# schematic.net
KiCad netlist of a schematic drawn in Altium Designer
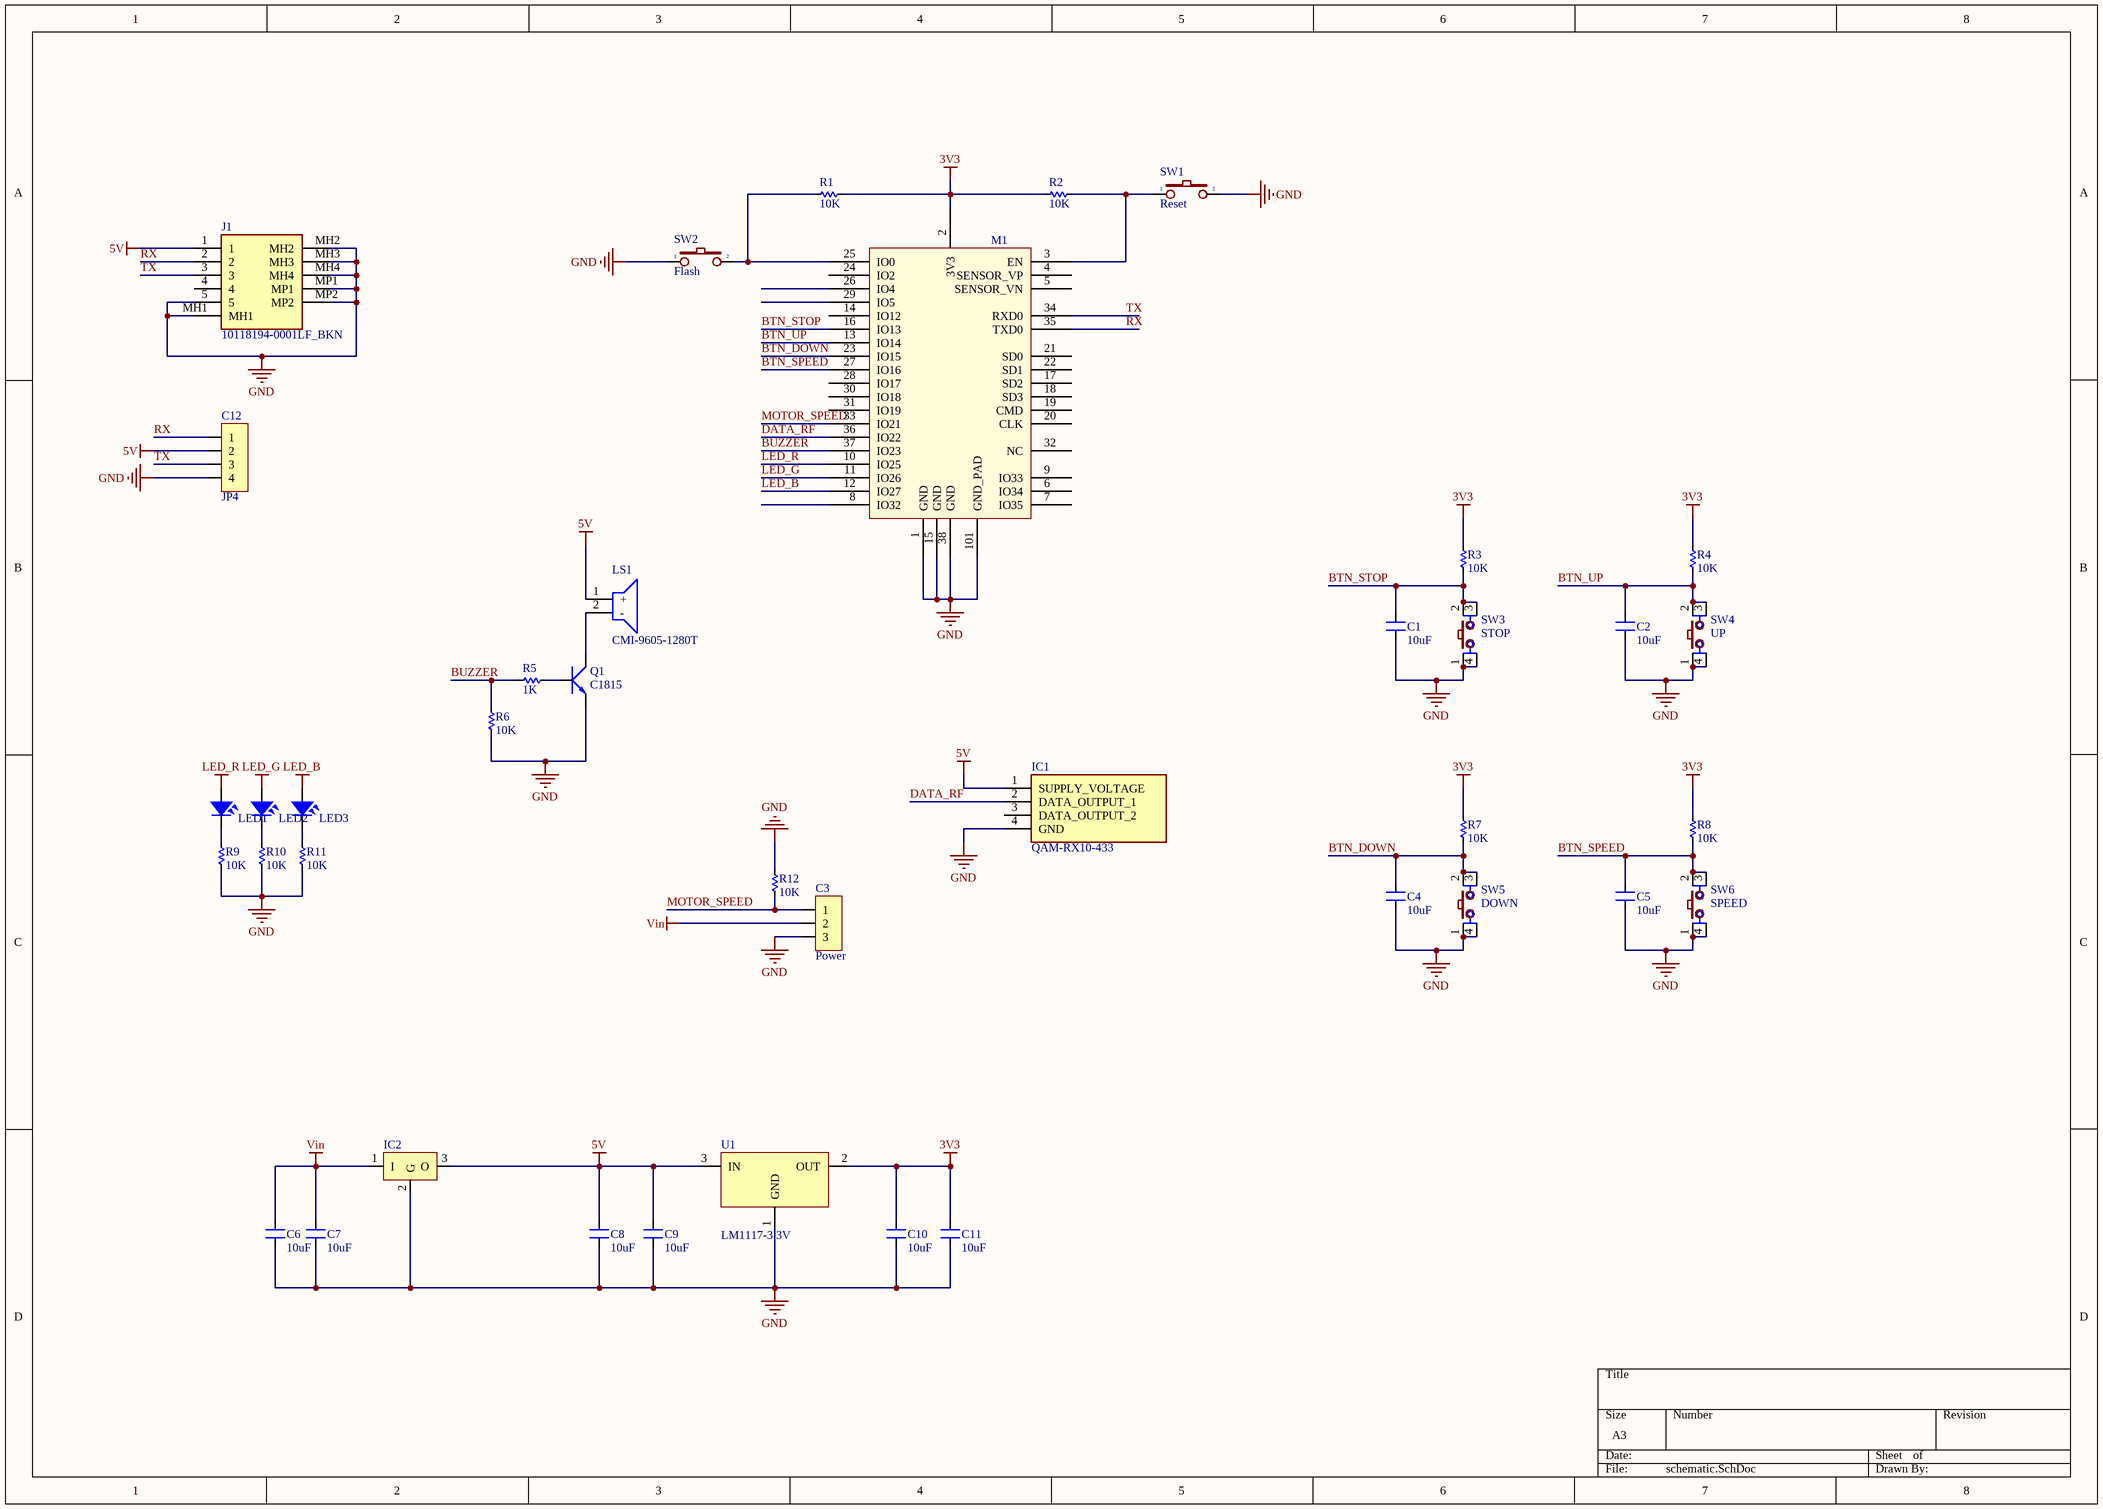
[diagram p0: schematic.SchDoc]

(export (version "E")
  (design (tool "Eeschema 10.0.6"))
  (components
    (comp (ref "C1")
      (value "10uF")
      (footprint "CN-SMD-0603")
      (description "Tu gom")
      (libsource (lib "LIBTanCN") (part "CN"))
    )
    (comp (ref "C2")
      (value "10uF")
      (footprint "CN-SMD-0603")
      (description "Tu gom")
      (libsource (lib "LIBTanCN") (part "CN"))
    )
    (comp (ref "C3")
      (value "Power")
      (footprint "JP3-D1C")
      (description "WR-PHD 2.54 mm Angled Socket Header")
      (fields
        (field (name "MANUFACTURER") "Würth Elektronik eiSos GmbH")
        (field (name "PARTNO") "613003143121")
        (field (name "CREATED BY") "Karrer Zheng")
      )
      (libsource (lib "LIBRARY") (part "JP3"))
    )
    (comp (ref "C4")
      (value "10uF")
      (footprint "CN-SMD-0603")
      (description "Tu gom")
      (libsource (lib "LIBTanCN") (part "CN"))
    )
    (comp (ref "C5")
      (value "10uF")
      (footprint "CN-SMD-0603")
      (description "Tu gom")
      (libsource (lib "LIBTanCN") (part "CN"))
    )
    (comp (ref "C6")
      (value "10uF")
      (footprint "CN-SMD-0603")
      (description "Tu gom")
      (libsource (lib "LIBTanCN") (part "CN"))
    )
    (comp (ref "C7")
      (value "10uF")
      (footprint "CN-SMD-0603")
      (description "Tu gom")
      (libsource (lib "LIBTanCN") (part "CN"))
    )
    (comp (ref "C8")
      (value "10uF")
      (footprint "CN-SMD-0603")
      (description "Tu gom")
      (libsource (lib "LIBTanCN") (part "CN"))
    )
    (comp (ref "C9")
      (value "10uF")
      (footprint "CN-SMD-0603")
      (description "Tu gom")
      (libsource (lib "LIBTanCN") (part "CN"))
    )
    (comp (ref "C10")
      (value "10uF")
      (footprint "CN-SMD-0603")
      (description "Tu gom")
      (libsource (lib "LIBTanCN") (part "CN"))
    )
    (comp (ref "C11")
      (value "10uF")
      (footprint "CN-SMD-0603")
      (description "Tu gom")
      (libsource (lib "LIBTanCN") (part "CN"))
    )
    (comp (ref "C12")
      (value "JP4")
      (footprint "JP4-C1T")
      (description "WR-PHD 2.54 mm Angled Socket Header")
      (fields
        (field (name "MANUFACTURER") "Würth Elektronik eiSos GmbH")
        (field (name "PARTNO") "613004143121")
        (field (name "CREATED BY") "Karrer Zheng")
      )
      (libsource (lib "LIBRARY") (part "JP4"))
    )
    (comp (ref "IC1")
      (value "QAM-RX10-433")
      (footprint "SamacSys:QAMRX10433")
      (description "Integrated Circuit")
      (fields (field (name "MOUSER PART NUMBER") "223-QAM-RX10-433"))
      (libsource (lib "*") (part "QAM-RX10-433"))
    )
    (comp (ref "IC2")
      (value "LM78xx")
      (footprint "TO252-123")
      (description "Positive Voltage Regulator")
      (fields (field (name "PUBLISHER") "Altium Limited"))
      (libsource (lib "LIBRARY") (part "LM78xx"))
    )
    (comp (ref "J1")
      (value "10118194-0001LF_BKN")
      (footprint "SamacSys:101181940001LFBKN")
      (description "Connector")
      (fields (field (name "MANUFACTURER_PART_NUMBER") "10118194-0001LF/BKN"))
      (libsource (lib "*") (part "10118194-0001LF_BKN"))
    )
    (comp (ref "LED1")
      (value "LED")
      (footprint "LED-3MM-BLUE")
      (description "LED Single colour Green and Red")
      (libsource (lib "LIBRARY") (part "LED"))
    )
    (comp (ref "LED2")
      (value "LED")
      (footprint "LED-3MM-BLUE")
      (description "LED Single colour Green and Red")
      (libsource (lib "LIBRARY") (part "LED"))
    )
    (comp (ref "LED3")
      (value "LED")
      (footprint "LED-3MM-BLUE")
      (description "LED Single colour Green and Red")
      (libsource (lib "LIBRARY") (part "LED"))
    )
    (comp (ref "LS1")
      (value "CMI-9605-1280T")
      (footprint "SamacSys:CMI96051280T")
      (description "Loudspeaker or Buzzer")
      (fields (field (name "MOUSER PART NUMBER") "490-CMI-9605-1280T"))
      (libsource (lib "SamacSys") (part "CMI-9605-1280T"))
    )
    (comp (ref "M1")
      (value "ESP32S_Module")
      (footprint "ESP32S")
      (description "Esp-32S")
      (libsource (lib "ESP32S") (part "ESP32S_Module"))
    )
    (comp (ref "Q1")
      (value "C1815")
      (footprint "SOT23B")
      (description "NPN 600mW, ECB")
      (libsource (lib "electronicvn-library1") (part "C1815"))
    )
    (comp (ref "R1")
      (value "10K")
      (footprint "RES-SMD-0603")
      (description "Resistor")
      (fields
        (field (name "MANUFACTURER") "Generic Components")
        (field (name "PUBLISHER") "Altium Hobart Technology Centre")
      )
      (libsource (lib "LIBRARY") (part "Res-SMD"))
    )
    (comp (ref "R2")
      (value "10K")
      (footprint "RES-SMD-0603")
      (description "Resistor")
      (fields
        (field (name "MANUFACTURER") "Generic Components")
        (field (name "PUBLISHER") "Altium Hobart Technology Centre")
      )
      (libsource (lib "LIBRARY") (part "Res-SMD"))
    )
    (comp (ref "R3")
      (value "10K")
      (footprint "RES-SMD-0603")
      (description "Resistor")
      (fields
        (field (name "MANUFACTURER") "Generic Components")
        (field (name "PUBLISHER") "Altium Hobart Technology Centre")
      )
      (libsource (lib "LIBRARY") (part "Res-SMD"))
    )
    (comp (ref "R4")
      (value "10K")
      (footprint "RES-SMD-0603")
      (description "Resistor")
      (fields
        (field (name "MANUFACTURER") "Generic Components")
        (field (name "PUBLISHER") "Altium Hobart Technology Centre")
      )
      (libsource (lib "LIBRARY") (part "Res-SMD"))
    )
    (comp (ref "R5")
      (value "1K")
      (footprint "RES-SMD-0603")
      (description "Resistor")
      (fields
        (field (name "MANUFACTURER") "Generic Components")
        (field (name "PUBLISHER") "Altium Hobart Technology Centre")
      )
      (libsource (lib "LIBRARY") (part "Res-SMD"))
    )
    (comp (ref "R6")
      (value "10K")
      (footprint "RES-SMD-0603")
      (description "Resistor")
      (fields
        (field (name "MANUFACTURER") "Generic Components")
        (field (name "PUBLISHER") "Altium Hobart Technology Centre")
      )
      (libsource (lib "LIBRARY") (part "Res-SMD"))
    )
    (comp (ref "R7")
      (value "10K")
      (footprint "RES-SMD-0603")
      (description "Resistor")
      (fields
        (field (name "MANUFACTURER") "Generic Components")
        (field (name "PUBLISHER") "Altium Hobart Technology Centre")
      )
      (libsource (lib "LIBRARY") (part "Res-SMD"))
    )
    (comp (ref "R8")
      (value "10K")
      (footprint "RES-SMD-0603")
      (description "Resistor")
      (fields
        (field (name "MANUFACTURER") "Generic Components")
        (field (name "PUBLISHER") "Altium Hobart Technology Centre")
      )
      (libsource (lib "LIBRARY") (part "Res-SMD"))
    )
    (comp (ref "R9")
      (value "10K")
      (footprint "RES-SMD-0603")
      (description "Resistor")
      (fields
        (field (name "MANUFACTURER") "Generic Components")
        (field (name "PUBLISHER") "Altium Hobart Technology Centre")
      )
      (libsource (lib "LIBRARY") (part "Res-SMD"))
    )
    (comp (ref "R10")
      (value "10K")
      (footprint "RES-SMD-0603")
      (description "Resistor")
      (fields
        (field (name "MANUFACTURER") "Generic Components")
        (field (name "PUBLISHER") "Altium Hobart Technology Centre")
      )
      (libsource (lib "LIBRARY") (part "Res-SMD"))
    )
    (comp (ref "R11")
      (value "10K")
      (footprint "RES-SMD-0603")
      (description "Resistor")
      (fields
        (field (name "MANUFACTURER") "Generic Components")
        (field (name "PUBLISHER") "Altium Hobart Technology Centre")
      )
      (libsource (lib "LIBRARY") (part "Res-SMD"))
    )
    (comp (ref "R12")
      (value "10K")
      (footprint "RES-SMD-0603")
      (description "Resistor")
      (fields
        (field (name "MANUFACTURER") "Generic Components")
        (field (name "PUBLISHER") "Altium Hobart Technology Centre")
      )
      (libsource (lib "LIBRARY") (part "Res-SMD"))
    )
    (comp (ref "SW1")
      (value "Reset")
      (footprint "SW1-SMD")
      (description "Switch button 2 pin")
      (libsource (lib "LIBRARY") (part "SW2"))
    )
    (comp (ref "SW2")
      (value "Flash")
      (footprint "SW-DIP1-1")
      (description "Switch button 2 pin")
      (libsource (lib "LIBRARY") (part "SW2"))
    )
    (comp (ref "SW3")
      (value "STOP")
      (footprint "SW2-SMD")
      (description "Switch button 4 pin")
      (libsource (lib "LIBRARY") (part "SW4"))
    )
    (comp (ref "SW4")
      (value "UP")
      (footprint "SW2-SMD")
      (description "Switch button 4 pin")
      (libsource (lib "LIBRARY") (part "SW4"))
    )
    (comp (ref "SW5")
      (value "DOWN")
      (footprint "SW2-SMD")
      (description "Switch button 4 pin")
      (libsource (lib "LIBRARY") (part "SW4"))
    )
    (comp (ref "SW6")
      (value "SPEED")
      (footprint "SW2-SMD")
      (description "Switch button 4 pin")
      (libsource (lib "LIBRARY") (part "SW4"))
    )
    (comp (ref "U1")
      (value "LM1117-3.3V")
      (footprint "SOT223")
      (description "800mA Low-Dropout Linear Regulator")
      (fields (field (name "CREATOR") "Nguyen Ba Bien"))
      (libsource (lib "LIBRARY") (part "LM1117"))
    )
  )
  (nets
    (net (code "1") (name "/BTN_DOWN") (class "Default")
      (node (ref "C4") (pin "1") (pinfunction "1_1") (pintype "passive"))
      (node (ref "M1") (pin "23") (pinfunction "IO15_23") (pintype "passive"))
      (node (ref "R7") (pin "2") (pinfunction "2_2") (pintype "passive"))
      (node (ref "SW5") (pin "2") (pinfunction "2_2") (pintype "passive"))
      (node (ref "SW5") (pin "3") (pinfunction "3_3") (pintype "passive"))
    )
    (net (code "2") (name "/BTN_SPEED") (class "Default")
      (node (ref "C5") (pin "1") (pinfunction "1_1") (pintype "passive"))
      (node (ref "M1") (pin "27") (pinfunction "IO16_27") (pintype "passive"))
      (node (ref "R8") (pin "2") (pinfunction "2_2") (pintype "passive"))
      (node (ref "SW6") (pin "2") (pinfunction "2_2") (pintype "passive"))
      (node (ref "SW6") (pin "3") (pinfunction "3_3") (pintype "passive"))
    )
    (net (code "3") (name "/BTN_STOP") (class "Default")
      (node (ref "C1") (pin "1") (pinfunction "1_1") (pintype "passive"))
      (node (ref "M1") (pin "16") (pinfunction "IO13_16") (pintype "passive"))
      (node (ref "R3") (pin "2") (pinfunction "2_2") (pintype "passive"))
      (node (ref "SW3") (pin "2") (pinfunction "2_2") (pintype "passive"))
      (node (ref "SW3") (pin "3") (pinfunction "3_3") (pintype "passive"))
    )
    (net (code "4") (name "/BTN_UP") (class "Default")
      (node (ref "C2") (pin "1") (pinfunction "1_1") (pintype "passive"))
      (node (ref "M1") (pin "13") (pinfunction "IO14_13") (pintype "passive"))
      (node (ref "R4") (pin "2") (pinfunction "2_2") (pintype "passive"))
      (node (ref "SW4") (pin "2") (pinfunction "2_2") (pintype "passive"))
      (node (ref "SW4") (pin "3") (pinfunction "3_3") (pintype "passive"))
    )
    (net (code "5") (name "/BUZZER") (class "Default")
      (node (ref "M1") (pin "37") (pinfunction "IO23_37") (pintype "passive"))
      (node (ref "R5") (pin "2") (pinfunction "2_2") (pintype "passive"))
      (node (ref "R6") (pin "1") (pinfunction "1_1") (pintype "passive"))
    )
    (net (code "6") (name "/DATA_RF") (class "Default")
      (node (ref "IC1") (pin "2") (pinfunction "DATA_OUTPUT_1_2") (pintype "passive"))
      (node (ref "M1") (pin "36") (pinfunction "IO22_36") (pintype "passive"))
    )
    (net (code "7") (name "/MOTOR_SPEED") (class "Default")
      (node (ref "C3") (pin "1") (pinfunction "1_1") (pintype "passive"))
      (node (ref "M1") (pin "33") (pinfunction "IO21_33") (pintype "passive"))
      (node (ref "R12") (pin "2") (pinfunction "2_2") (pintype "passive"))
    )
    (net (code "8") (name "/RX") (class "Default")
      (node (ref "C12") (pin "1") (pinfunction "1_1") (pintype "passive"))
      (node (ref "J1") (pin "2") (pinfunction "2_2") (pintype "passive"))
      (node (ref "M1") (pin "35") (pinfunction "TXD0_35") (pintype "passive"))
    )
    (net (code "9") (name "/TX") (class "Default")
      (node (ref "C12") (pin "3") (pinfunction "3_3") (pintype "passive"))
      (node (ref "J1") (pin "3") (pinfunction "3_3") (pintype "passive"))
      (node (ref "M1") (pin "34") (pinfunction "RXD0_34") (pintype "passive"))
    )
    (net (code "10") (name "3V3") (class "Default")
      (node (ref "C10") (pin "1") (pinfunction "1_1") (pintype "passive"))
      (node (ref "C11") (pin "1") (pinfunction "1_1") (pintype "passive"))
      (node (ref "M1") (pin "2") (pinfunction "3V3_2") (pintype "power_in"))
      (node (ref "R1") (pin "1") (pinfunction "1_1") (pintype "passive"))
      (node (ref "R2") (pin "2") (pinfunction "2_2") (pintype "passive"))
      (node (ref "R3") (pin "1") (pinfunction "1_1") (pintype "passive"))
      (node (ref "R4") (pin "1") (pinfunction "1_1") (pintype "passive"))
      (node (ref "R7") (pin "1") (pinfunction "1_1") (pintype "passive"))
      (node (ref "R8") (pin "1") (pinfunction "1_1") (pintype "passive"))
      (node (ref "U1") (pin "2") (pinfunction "OUT_2") (pintype "passive"))
    )
    (net (code "11") (name "5V") (class "Default")
      (node (ref "C12") (pin "2") (pinfunction "2_2") (pintype "passive"))
      (node (ref "C8") (pin "1") (pinfunction "1_1") (pintype "passive"))
      (node (ref "C9") (pin "1") (pinfunction "1_1") (pintype "passive"))
      (node (ref "IC1") (pin "1") (pinfunction "SUPPLY_VOLTAGE_1") (pintype "passive"))
      (node (ref "IC2") (pin "3") (pinfunction "O_3") (pintype "power_in"))
      (node (ref "J1") (pin "1") (pinfunction "1_1") (pintype "passive"))
      (node (ref "LS1") (pin "1") (pinfunction "+_1") (pintype "passive"))
      (node (ref "U1") (pin "3") (pinfunction "IN_3") (pintype "passive"))
    )
    (net (code "12") (name "GND") (class "Default")
      (node (ref "C1") (pin "2") (pinfunction "2_2") (pintype "passive"))
      (node (ref "C10") (pin "2") (pinfunction "2_2") (pintype "passive"))
      (node (ref "C11") (pin "2") (pinfunction "2_2") (pintype "passive"))
      (node (ref "C12") (pin "4") (pinfunction "4_4") (pintype "passive"))
      (node (ref "C2") (pin "2") (pinfunction "2_2") (pintype "passive"))
      (node (ref "C3") (pin "3") (pinfunction "3_3") (pintype "passive"))
      (node (ref "C4") (pin "2") (pinfunction "2_2") (pintype "passive"))
      (node (ref "C5") (pin "2") (pinfunction "2_2") (pintype "passive"))
      (node (ref "C6") (pin "2") (pinfunction "2_2") (pintype "passive"))
      (node (ref "C7") (pin "2") (pinfunction "2_2") (pintype "passive"))
      (node (ref "C8") (pin "2") (pinfunction "2_2") (pintype "passive"))
      (node (ref "C9") (pin "2") (pinfunction "2_2") (pintype "passive"))
      (node (ref "IC1") (pin "4") (pinfunction "GND_4") (pintype "passive"))
      (node (ref "IC2") (pin "2") (pinfunction "G_2") (pintype "power_in"))
      (node (ref "J1") (pin "5") (pinfunction "5_5") (pintype "passive"))
      (node (ref "J1") (pin "MH1") (pinfunction "MH1_MH1") (pintype "passive"))
      (node (ref "J1") (pin "MH2") (pinfunction "MH2_MH2") (pintype "passive"))
      (node (ref "J1") (pin "MH3") (pinfunction "MH3_MH3") (pintype "passive"))
      (node (ref "J1") (pin "MH4") (pinfunction "MH4_MH4") (pintype "passive"))
      (node (ref "J1") (pin "MP1") (pinfunction "MP1_MP1") (pintype "passive"))
      (node (ref "J1") (pin "MP2") (pinfunction "MP2_MP2") (pintype "passive"))
      (node (ref "M1") (pin "1") (pinfunction "GND_1") (pintype "power_in"))
      (node (ref "M1") (pin "101") (pinfunction "GND_PAD_101") (pintype "power_in"))
      (node (ref "M1") (pin "15") (pinfunction "GND_15") (pintype "power_in"))
      (node (ref "M1") (pin "38") (pinfunction "GND_38") (pintype "power_in"))
      (node (ref "Q1") (pin "1") (pinfunction "E_1") (pintype "passive"))
      (node (ref "R10") (pin "1") (pinfunction "1_1") (pintype "passive"))
      (node (ref "R11") (pin "1") (pinfunction "1_1") (pintype "passive"))
      (node (ref "R12") (pin "1") (pinfunction "1_1") (pintype "passive"))
      (node (ref "R6") (pin "2") (pinfunction "2_2") (pintype "passive"))
      (node (ref "R9") (pin "1") (pinfunction "1_1") (pintype "passive"))
      (node (ref "SW1") (pin "2") (pinfunction "2_2") (pintype "passive"))
      (node (ref "SW2") (pin "1") (pinfunction "1_1") (pintype "passive"))
      (node (ref "SW3") (pin "1") (pintype "passive"))
      (node (ref "SW3") (pin "4") (pinfunction "4_4") (pintype "passive"))
      (node (ref "SW4") (pin "1") (pintype "passive"))
      (node (ref "SW4") (pin "4") (pinfunction "4_4") (pintype "passive"))
      (node (ref "SW5") (pin "1") (pintype "passive"))
      (node (ref "SW5") (pin "4") (pinfunction "4_4") (pintype "passive"))
      (node (ref "SW6") (pin "1") (pintype "passive"))
      (node (ref "SW6") (pin "4") (pinfunction "4_4") (pintype "passive"))
      (node (ref "U1") (pin "1") (pinfunction "GND_1") (pintype "passive"))
    )
    (net (code "13") (name "LED_B") (class "Default")
      (node (ref "LED3") (pin "1") (pinfunction "1_1") (pintype "passive"))
      (node (ref "M1") (pin "12") (pinfunction "IO27_12") (pintype "passive"))
    )
    (net (code "14") (name "LED_G") (class "Default")
      (node (ref "LED2") (pin "1") (pinfunction "1_1") (pintype "passive"))
      (node (ref "M1") (pin "11") (pinfunction "IO26_11") (pintype "passive"))
    )
    (net (code "15") (name "LED_R") (class "Default")
      (node (ref "LED1") (pin "1") (pinfunction "1_1") (pintype "passive"))
      (node (ref "M1") (pin "10") (pinfunction "IO25_10") (pintype "passive"))
    )
    (net (code "16") (name "Net-(LED1-Pad2)") (class "Default")
      (node (ref "LED1") (pin "2") (pinfunction "2_2") (pintype "passive"))
      (node (ref "R9") (pin "2") (pinfunction "2_2") (pintype "passive"))
    )
    (net (code "17") (name "Net-(LED2-Pad2)") (class "Default")
      (node (ref "LED2") (pin "2") (pinfunction "2_2") (pintype "passive"))
      (node (ref "R10") (pin "2") (pinfunction "2_2") (pintype "passive"))
    )
    (net (code "18") (name "Net-(LED3-Pad2)") (class "Default")
      (node (ref "LED3") (pin "2") (pinfunction "2_2") (pintype "passive"))
      (node (ref "R11") (pin "2") (pinfunction "2_2") (pintype "passive"))
    )
    (net (code "19") (name "Net-(LS1--)") (class "Default")
      (node (ref "LS1") (pin "2") (pinfunction "-_2") (pintype "passive"))
      (node (ref "Q1") (pin "2") (pinfunction "C_2") (pintype "passive"))
    )
    (net (code "20") (name "Net-(M1-EN)") (class "Default")
      (node (ref "M1") (pin "3") (pinfunction "EN_3") (pintype "power_in"))
      (node (ref "R2") (pin "1") (pinfunction "1_1") (pintype "passive"))
      (node (ref "SW1") (pin "1") (pinfunction "1_1") (pintype "passive"))
    )
    (net (code "21") (name "Net-(M1-IO0)") (class "Default")
      (node (ref "M1") (pin "25") (pinfunction "IO0_25") (pintype "passive"))
      (node (ref "R1") (pin "2") (pinfunction "2_2") (pintype "passive"))
      (node (ref "SW2") (pin "2") (pinfunction "2_2") (pintype "passive"))
    )
    (net (code "22") (name "Net-(Q1-B)") (class "Default")
      (node (ref "Q1") (pin "3") (pinfunction "B_3") (pintype "passive"))
      (node (ref "R5") (pin "1") (pinfunction "1_1") (pintype "passive"))
    )
    (net (code "23") (name "Vin") (class "Default")
      (node (ref "C3") (pin "2") (pinfunction "2_2") (pintype "passive"))
      (node (ref "C6") (pin "1") (pinfunction "1_1") (pintype "passive"))
      (node (ref "C7") (pin "1") (pinfunction "1_1") (pintype "passive"))
      (node (ref "IC2") (pin "1") (pinfunction "I_1") (pintype "power_in"))
    )
    (net (code "24") (name "unconnected-(IC1-DATA_OUTPUT_2-Pad3)") (class "Default")
      (node (ref "IC1") (pin "3") (pinfunction "DATA_OUTPUT_2_3") (pintype "passive"))
    )
    (net (code "25") (name "unconnected-(J1-Pad4)") (class "Default")
      (node (ref "J1") (pin "4") (pinfunction "4_4") (pintype "passive"))
    )
    (net (code "26") (name "unconnected-(M1-CLK-Pad20)") (class "Default")
      (node (ref "M1") (pin "20") (pinfunction "CLK_20") (pintype "passive"))
    )
    (net (code "27") (name "unconnected-(M1-CMD-Pad19)") (class "Default")
      (node (ref "M1") (pin "19") (pinfunction "CMD_19") (pintype "passive"))
    )
    (net (code "28") (name "unconnected-(M1-IO2-Pad24)") (class "Default")
      (node (ref "M1") (pin "24") (pinfunction "IO2_24") (pintype "passive"))
    )
    (net (code "29") (name "unconnected-(M1-IO4-Pad26)") (class "Default")
      (node (ref "M1") (pin "26") (pinfunction "IO4_26") (pintype "passive"))
    )
    (net (code "30") (name "unconnected-(M1-IO5-Pad29)") (class "Default")
      (node (ref "M1") (pin "29") (pinfunction "IO5_29") (pintype "passive"))
    )
    (net (code "31") (name "unconnected-(M1-IO12-Pad14)") (class "Default")
      (node (ref "M1") (pin "14") (pinfunction "IO12_14") (pintype "passive"))
    )
    (net (code "32") (name "unconnected-(M1-IO17-Pad28)") (class "Default")
      (node (ref "M1") (pin "28") (pinfunction "IO17_28") (pintype "passive"))
    )
    (net (code "33") (name "unconnected-(M1-IO18-Pad30)") (class "Default")
      (node (ref "M1") (pin "30") (pinfunction "IO18_30") (pintype "passive"))
    )
    (net (code "34") (name "unconnected-(M1-IO19-Pad31)") (class "Default")
      (node (ref "M1") (pin "31") (pinfunction "IO19_31") (pintype "passive"))
    )
    (net (code "35") (name "unconnected-(M1-IO32-Pad8)") (class "Default")
      (node (ref "M1") (pin "8") (pinfunction "IO32_8") (pintype "passive"))
    )
    (net (code "36") (name "unconnected-(M1-IO33-Pad9)") (class "Default")
      (node (ref "M1") (pin "9") (pinfunction "IO33_9") (pintype "passive"))
    )
    (net (code "37") (name "unconnected-(M1-IO34-Pad6)") (class "Default")
      (node (ref "M1") (pin "6") (pinfunction "IO34_6") (pintype "passive"))
    )
    (net (code "38") (name "unconnected-(M1-IO35-Pad7)") (class "Default")
      (node (ref "M1") (pin "7") (pinfunction "IO35_7") (pintype "passive"))
    )
    (net (code "39") (name "unconnected-(M1-NC-Pad32)") (class "Default")
      (node (ref "M1") (pin "32") (pinfunction "NC_32") (pintype "passive"))
    )
    (net (code "40") (name "unconnected-(M1-SD0-Pad21)") (class "Default")
      (node (ref "M1") (pin "21") (pinfunction "SD0_21") (pintype "passive"))
    )
    (net (code "41") (name "unconnected-(M1-SD1-Pad22)") (class "Default")
      (node (ref "M1") (pin "22") (pinfunction "SD1_22") (pintype "passive"))
    )
    (net (code "42") (name "unconnected-(M1-SD2-Pad17)") (class "Default")
      (node (ref "M1") (pin "17") (pinfunction "SD2_17") (pintype "passive"))
    )
    (net (code "43") (name "unconnected-(M1-SD3-Pad18)") (class "Default")
      (node (ref "M1") (pin "18") (pinfunction "SD3_18") (pintype "passive"))
    )
    (net (code "44") (name "unconnected-(M1-SENSOR_VN-Pad5)") (class "Default")
      (node (ref "M1") (pin "5") (pinfunction "SENSOR_VN_5") (pintype "passive"))
    )
    (net (code "45") (name "unconnected-(M1-SENSOR_VP-Pad4)") (class "Default")
      (node (ref "M1") (pin "4") (pinfunction "SENSOR_VP_4") (pintype "passive"))
    )
  )
)
